# user_interface.net
KiCad netlist of a schematic drawn in Altium Designer
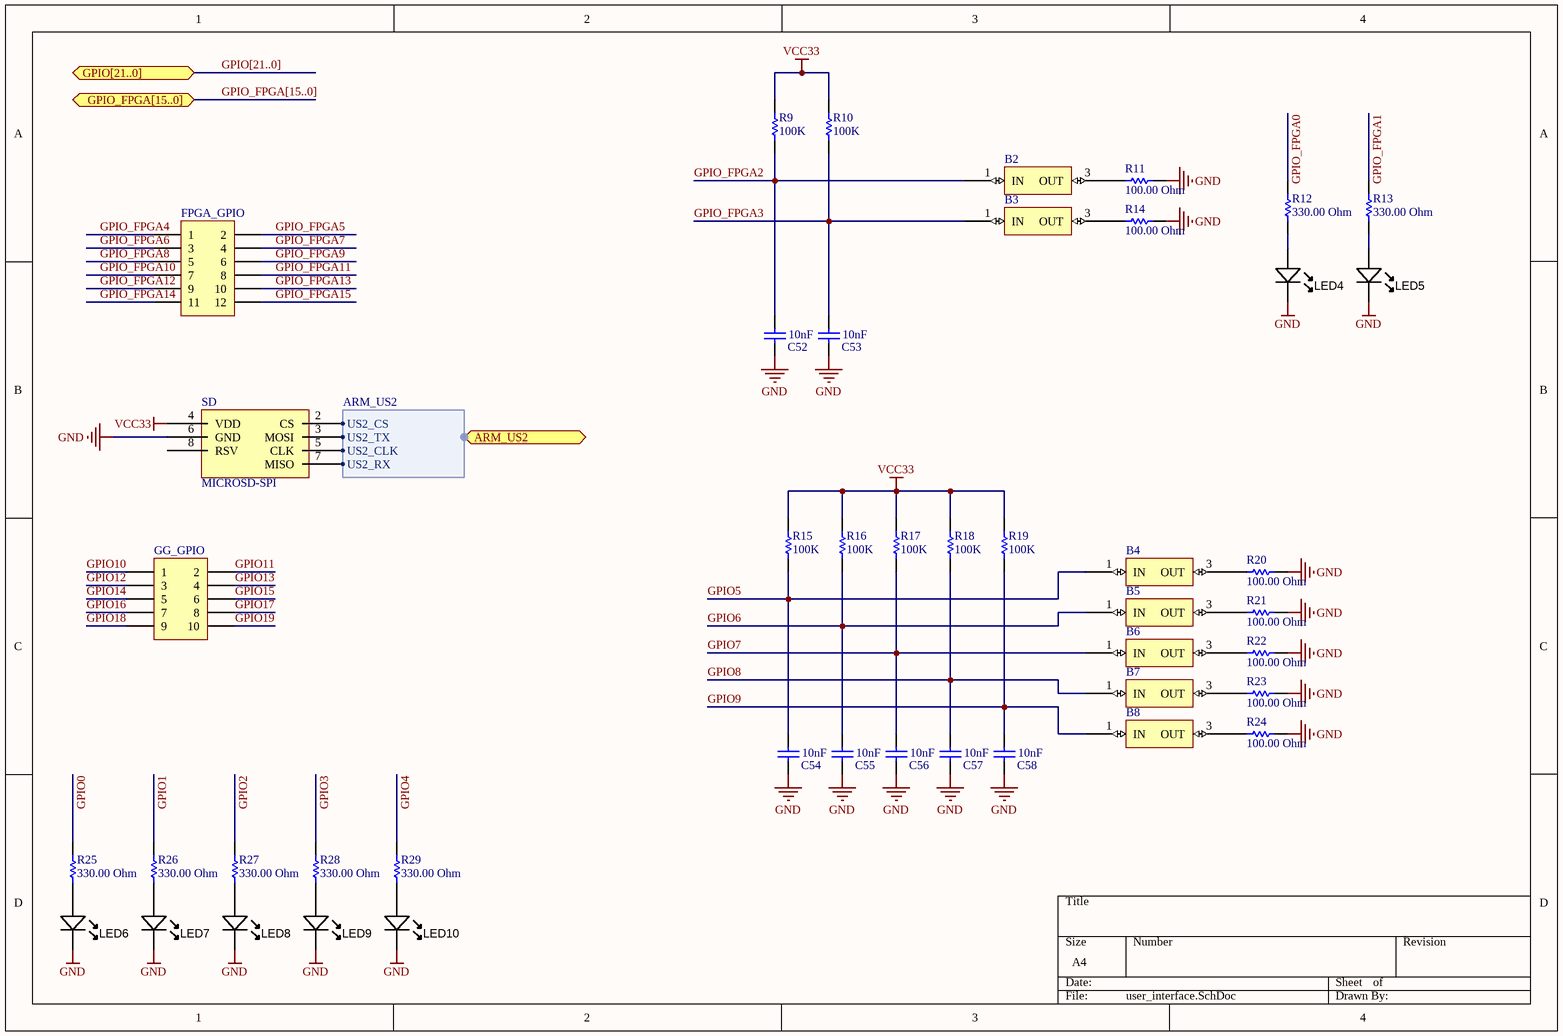
[diagram p0: user_interface.SchDoc]

(export (version "E")
  (design (tool "Eeschema 10.0.6"))
  (components
    (comp (ref "B2") (value "BUTTON") (footprint "BUTTON") (libsource (lib "PowerConnector") (part "BUTTON")))
    (comp (ref "B3") (value "BUTTON") (footprint "BUTTON") (libsource (lib "PowerConnector") (part "BUTTON")))
    (comp (ref "B4") (value "BUTTON") (footprint "BUTTON") (libsource (lib "PowerConnector") (part "BUTTON")))
    (comp (ref "B5") (value "BUTTON") (footprint "BUTTON") (libsource (lib "PowerConnector") (part "BUTTON")))
    (comp (ref "B6") (value "BUTTON") (footprint "BUTTON") (libsource (lib "PowerConnector") (part "BUTTON")))
    (comp (ref "B7") (value "BUTTON") (footprint "BUTTON") (libsource (lib "PowerConnector") (part "BUTTON")))
    (comp (ref "B8") (value "BUTTON") (footprint "BUTTON") (libsource (lib "PowerConnector") (part "BUTTON")))
    (comp (ref "C52")
      (value "10nF")
      (footprint "CAPC0805(2012)75_N")
      (description "CAP 10nF 50V ±10% 0805 (2012 Metric) Thickness 0.75mm SMD")
      (fields (field (name "TOLERANCE") "±10%"))
      (libsource (lib "Altium Content Vault") (part "CMP-1036-03842-1"))
    )
    (comp (ref "C53")
      (value "10nF")
      (footprint "CAPC0805(2012)75_N")
      (description "CAP 10nF 50V ±10% 0805 (2012 Metric) Thickness 0.75mm SMD")
      (fields (field (name "TOLERANCE") "±10%"))
      (libsource (lib "Altium Content Vault") (part "CMP-1036-03842-1"))
    )
    (comp (ref "C54")
      (value "10nF")
      (footprint "CAPC0805(2012)75_N")
      (description "CAP 10nF 50V ±10% 0805 (2012 Metric) Thickness 0.75mm SMD")
      (fields (field (name "TOLERANCE") "±10%"))
      (libsource (lib "Altium Content Vault") (part "CMP-1036-03842-1"))
    )
    (comp (ref "C55")
      (value "10nF")
      (footprint "CAPC0805(2012)75_N")
      (description "CAP 10nF 50V ±10% 0805 (2012 Metric) Thickness 0.75mm SMD")
      (fields (field (name "TOLERANCE") "±10%"))
      (libsource (lib "Altium Content Vault") (part "CMP-1036-03842-1"))
    )
    (comp (ref "C56")
      (value "10nF")
      (footprint "CAPC0805(2012)75_N")
      (description "CAP 10nF 50V ±10% 0805 (2012 Metric) Thickness 0.75mm SMD")
      (fields (field (name "TOLERANCE") "±10%"))
      (libsource (lib "Altium Content Vault") (part "CMP-1036-03842-1"))
    )
    (comp (ref "C57")
      (value "10nF")
      (footprint "CAPC0805(2012)75_N")
      (description "CAP 10nF 50V ±10% 0805 (2012 Metric) Thickness 0.75mm SMD")
      (fields (field (name "TOLERANCE") "±10%"))
      (libsource (lib "Altium Content Vault") (part "CMP-1036-03842-1"))
    )
    (comp (ref "C58")
      (value "10nF")
      (footprint "CAPC0805(2012)75_N")
      (description "CAP 10nF 50V ±10% 0805 (2012 Metric) Thickness 0.75mm SMD")
      (fields (field (name "TOLERANCE") "±10%"))
      (libsource (lib "Altium Content Vault") (part "CMP-1036-03842-1"))
    )
    (comp (ref "FPGA_GPIO")
      (value "Header 6X2")
      (footprint "HDR2X6")
      (description "Header, 6-Pin, Dual row")
      (fields (field (name "PUBLISHER") "Altium Limited"))
      (libsource (lib "Miscellaneous Connectors") (part "Header 6X2"))
    )
    (comp (ref "GG_GPIO")
      (value "Header 5X2")
      (footprint "HDR2X5")
      (description "Header, 5-Pin, Dual row")
      (fields (field (name "PUBLISHER") "Altium Limited"))
      (libsource (lib "Miscellaneous Connectors") (part "Header 5X2"))
    )
    (comp (ref "LED4")
      (value "Green")
      (footprint "LED-0805-K")
      (description "LED, 0805 SMD, Green")
      (libsource (lib "PBL - Light Sources") (part "LED_SMD_Green_0805"))
    )
    (comp (ref "LED5")
      (value "Green")
      (footprint "LED-0805-K")
      (description "LED, 0805 SMD, Green")
      (libsource (lib "PBL - Light Sources") (part "LED_SMD_Green_0805"))
    )
    (comp (ref "LED6")
      (value "Green")
      (footprint "LED-0805-K")
      (description "LED, 0805 SMD, Green")
      (libsource (lib "PBL - Light Sources") (part "LED_SMD_Green_0805"))
    )
    (comp (ref "LED7")
      (value "Green")
      (footprint "LED-0805-K")
      (description "LED, 0805 SMD, Green")
      (libsource (lib "PBL - Light Sources") (part "LED_SMD_Green_0805"))
    )
    (comp (ref "LED8")
      (value "Green")
      (footprint "LED-0805-K")
      (description "LED, 0805 SMD, Green")
      (libsource (lib "PBL - Light Sources") (part "LED_SMD_Green_0805"))
    )
    (comp (ref "LED9")
      (value "Green")
      (footprint "LED-0805-K")
      (description "LED, 0805 SMD, Green")
      (libsource (lib "PBL - Light Sources") (part "LED_SMD_Green_0805"))
    )
    (comp (ref "LED10")
      (value "Green")
      (footprint "LED-0805-K")
      (description "LED, 0805 SMD, Green")
      (libsource (lib "PBL - Light Sources") (part "LED_SMD_Green_0805"))
    )
    (comp (ref "R9")
      (value "100K")
      (footprint "RESC0805(2012)_L")
      (description "100K 0.125W 5% 0805 (2012 Metric)  SMD")
      (fields (field (name "TOLERANCE") "5 %") (field (name "POWER") "0.125 W"))
      (libsource (lib "Altium Content Vault") (part "CMP-1013-00122-1"))
    )
    (comp (ref "R10")
      (value "100K")
      (footprint "RESC0805(2012)_L")
      (description "100K 0.125W 5% 0805 (2012 Metric)  SMD")
      (fields (field (name "TOLERANCE") "5 %") (field (name "POWER") "0.125 W"))
      (libsource (lib "Altium Content Vault") (part "CMP-1013-00122-1"))
    )
    (comp (ref "R11")
      (value "100.00 Ohm")
      (footprint "RESC0805(2012)_M")
      (description "100R 0.125W 5% 0805 (2012 Metric)  SMD")
      (fields (field (name "TOLERANCE") "5 %") (field (name "POWER") "0.125 W"))
      (libsource (lib "Altium Content Vault") (part "CMP-1013-00050-1"))
    )
    (comp (ref "R12")
      (value "330.00 Ohm")
      (footprint "RESC0805(2012)_M")
      (description "330R 0.125W 1% 0805 (2012 Metric)  SMD")
      (fields (field (name "POWER") "0.125 W") (field (name "TOLERANCE") "1 %"))
      (libsource (lib "Altium Content Vault") (part "CMP-1013-00454-1"))
    )
    (comp (ref "R13")
      (value "330.00 Ohm")
      (footprint "RESC0805(2012)_M")
      (description "330R 0.125W 1% 0805 (2012 Metric)  SMD")
      (fields (field (name "POWER") "0.125 W") (field (name "TOLERANCE") "1 %"))
      (libsource (lib "Altium Content Vault") (part "CMP-1013-00454-1"))
    )
    (comp (ref "R14")
      (value "100.00 Ohm")
      (footprint "RESC0805(2012)_M")
      (description "100R 0.125W 5% 0805 (2012 Metric)  SMD")
      (fields (field (name "TOLERANCE") "5 %") (field (name "POWER") "0.125 W"))
      (libsource (lib "Altium Content Vault") (part "CMP-1013-00050-1"))
    )
    (comp (ref "R15")
      (value "100K")
      (footprint "RESC0805(2012)_L")
      (description "100K 0.125W 5% 0805 (2012 Metric)  SMD")
      (fields (field (name "TOLERANCE") "5 %") (field (name "POWER") "0.125 W"))
      (libsource (lib "Altium Content Vault") (part "CMP-1013-00122-1"))
    )
    (comp (ref "R16")
      (value "100K")
      (footprint "RESC0805(2012)_L")
      (description "100K 0.125W 5% 0805 (2012 Metric)  SMD")
      (fields (field (name "TOLERANCE") "5 %") (field (name "POWER") "0.125 W"))
      (libsource (lib "Altium Content Vault") (part "CMP-1013-00122-1"))
    )
    (comp (ref "R17")
      (value "100K")
      (footprint "RESC0805(2012)_L")
      (description "100K 0.125W 5% 0805 (2012 Metric)  SMD")
      (fields (field (name "TOLERANCE") "5 %") (field (name "POWER") "0.125 W"))
      (libsource (lib "Altium Content Vault") (part "CMP-1013-00122-1"))
    )
    (comp (ref "R18")
      (value "100K")
      (footprint "RESC0805(2012)_L")
      (description "100K 0.125W 5% 0805 (2012 Metric)  SMD")
      (fields (field (name "TOLERANCE") "5 %") (field (name "POWER") "0.125 W"))
      (libsource (lib "Altium Content Vault") (part "CMP-1013-00122-1"))
    )
    (comp (ref "R19")
      (value "100K")
      (footprint "RESC0805(2012)_L")
      (description "100K 0.125W 5% 0805 (2012 Metric)  SMD")
      (fields (field (name "TOLERANCE") "5 %") (field (name "POWER") "0.125 W"))
      (libsource (lib "Altium Content Vault") (part "CMP-1013-00122-1"))
    )
    (comp (ref "R20")
      (value "100.00 Ohm")
      (footprint "RESC0805(2012)_M")
      (description "100R 0.125W 5% 0805 (2012 Metric)  SMD")
      (fields (field (name "TOLERANCE") "5 %") (field (name "POWER") "0.125 W"))
      (libsource (lib "Altium Content Vault") (part "CMP-1013-00050-1"))
    )
    (comp (ref "R21")
      (value "100.00 Ohm")
      (footprint "RESC0805(2012)_M")
      (description "100R 0.125W 5% 0805 (2012 Metric)  SMD")
      (fields (field (name "TOLERANCE") "5 %") (field (name "POWER") "0.125 W"))
      (libsource (lib "Altium Content Vault") (part "CMP-1013-00050-1"))
    )
    (comp (ref "R22")
      (value "100.00 Ohm")
      (footprint "RESC0805(2012)_M")
      (description "100R 0.125W 5% 0805 (2012 Metric)  SMD")
      (fields (field (name "TOLERANCE") "5 %") (field (name "POWER") "0.125 W"))
      (libsource (lib "Altium Content Vault") (part "CMP-1013-00050-1"))
    )
    (comp (ref "R23")
      (value "100.00 Ohm")
      (footprint "RESC0805(2012)_M")
      (description "100R 0.125W 5% 0805 (2012 Metric)  SMD")
      (fields (field (name "TOLERANCE") "5 %") (field (name "POWER") "0.125 W"))
      (libsource (lib "Altium Content Vault") (part "CMP-1013-00050-1"))
    )
    (comp (ref "R24")
      (value "100.00 Ohm")
      (footprint "RESC0805(2012)_M")
      (description "100R 0.125W 5% 0805 (2012 Metric)  SMD")
      (fields (field (name "TOLERANCE") "5 %") (field (name "POWER") "0.125 W"))
      (libsource (lib "Altium Content Vault") (part "CMP-1013-00050-1"))
    )
    (comp (ref "R25")
      (value "330.00 Ohm")
      (footprint "RESC0805(2012)_M")
      (description "330R 0.125W 1% 0805 (2012 Metric)  SMD")
      (fields (field (name "POWER") "0.125 W") (field (name "TOLERANCE") "1 %"))
      (libsource (lib "Altium Content Vault") (part "CMP-1013-00454-1"))
    )
    (comp (ref "R26")
      (value "330.00 Ohm")
      (footprint "RESC0805(2012)_M")
      (description "330R 0.125W 1% 0805 (2012 Metric)  SMD")
      (fields (field (name "POWER") "0.125 W") (field (name "TOLERANCE") "1 %"))
      (libsource (lib "Altium Content Vault") (part "CMP-1013-00454-1"))
    )
    (comp (ref "R27")
      (value "330.00 Ohm")
      (footprint "RESC0805(2012)_M")
      (description "330R 0.125W 1% 0805 (2012 Metric)  SMD")
      (fields (field (name "POWER") "0.125 W") (field (name "TOLERANCE") "1 %"))
      (libsource (lib "Altium Content Vault") (part "CMP-1013-00454-1"))
    )
    (comp (ref "R28")
      (value "330.00 Ohm")
      (footprint "RESC0805(2012)_M")
      (description "330R 0.125W 1% 0805 (2012 Metric)  SMD")
      (fields (field (name "POWER") "0.125 W") (field (name "TOLERANCE") "1 %"))
      (libsource (lib "Altium Content Vault") (part "CMP-1013-00454-1"))
    )
    (comp (ref "R29")
      (value "330.00 Ohm")
      (footprint "RESC0805(2012)_M")
      (description "330R 0.125W 1% 0805 (2012 Metric)  SMD")
      (fields (field (name "POWER") "0.125 W") (field (name "TOLERANCE") "1 %"))
      (libsource (lib "Altium Content Vault") (part "CMP-1013-00454-1"))
    )
    (comp (ref "SD")
      (value "MICROSD-SPI")
      (footprint "MICROSD_WR-CRD")
      (libsource (lib "MICROSD") (part "MICROSD-SPI"))
    )
  )
  (nets
    (net (code "4") (name "/GPIO0") (class "Default")
      (node (ref "R25") (pin "2") (pinfunction "2_2") (pintype "passive"))
    )
    (net (code "5") (name "/GPIO1") (class "Default")
      (node (ref "R26") (pin "2") (pinfunction "2_2") (pintype "passive"))
    )
    (net (code "6") (name "/GPIO2") (class "Default")
      (node (ref "R27") (pin "2") (pinfunction "2_2") (pintype "passive"))
    )
    (net (code "7") (name "/GPIO3") (class "Default")
      (node (ref "R28") (pin "2") (pinfunction "2_2") (pintype "passive"))
    )
    (net (code "8") (name "/GPIO4") (class "Default")
      (node (ref "R29") (pin "2") (pinfunction "2_2") (pintype "passive"))
    )
    (net (code "9") (name "/GPIO5") (class "Default")
      (node (ref "B4") (pin "1") (pinfunction "IN_1") (pintype "bidirectional"))
      (node (ref "C54") (pin "2") (pinfunction "2_2") (pintype "passive"))
      (node (ref "R15") (pin "1") (pinfunction "1_1") (pintype "passive"))
    )
    (net (code "10") (name "/GPIO6") (class "Default")
      (node (ref "B5") (pin "1") (pinfunction "IN_1") (pintype "bidirectional"))
      (node (ref "C55") (pin "2") (pinfunction "2_2") (pintype "passive"))
      (node (ref "R16") (pin "1") (pinfunction "1_1") (pintype "passive"))
    )
    (net (code "11") (name "/GPIO7") (class "Default")
      (node (ref "B6") (pin "1") (pinfunction "IN_1") (pintype "bidirectional"))
      (node (ref "C56") (pin "2") (pinfunction "2_2") (pintype "passive"))
      (node (ref "R17") (pin "1") (pinfunction "1_1") (pintype "passive"))
    )
    (net (code "12") (name "/GPIO8") (class "Default")
      (node (ref "B7") (pin "1") (pinfunction "IN_1") (pintype "bidirectional"))
      (node (ref "C57") (pin "2") (pinfunction "2_2") (pintype "passive"))
      (node (ref "R18") (pin "1") (pinfunction "1_1") (pintype "passive"))
    )
    (net (code "13") (name "/GPIO9") (class "Default")
      (node (ref "B8") (pin "1") (pinfunction "IN_1") (pintype "bidirectional"))
      (node (ref "C58") (pin "2") (pinfunction "2_2") (pintype "passive"))
      (node (ref "R19") (pin "1") (pinfunction "1_1") (pintype "passive"))
    )
    (net (code "14") (name "/GPIO10") (class "Default")
      (node (ref "GG_GPIO") (pin "1") (pinfunction "1_1") (pintype "passive"))
    )
    (net (code "15") (name "/GPIO11") (class "Default")
      (node (ref "GG_GPIO") (pin "2") (pinfunction "2_2") (pintype "passive"))
    )
    (net (code "16") (name "/GPIO12") (class "Default")
      (node (ref "GG_GPIO") (pin "3") (pinfunction "3_3") (pintype "passive"))
    )
    (net (code "17") (name "/GPIO13") (class "Default")
      (node (ref "GG_GPIO") (pin "4") (pinfunction "4_4") (pintype "passive"))
    )
    (net (code "18") (name "/GPIO14") (class "Default")
      (node (ref "GG_GPIO") (pin "5") (pinfunction "5_5") (pintype "passive"))
    )
    (net (code "19") (name "/GPIO15") (class "Default")
      (node (ref "GG_GPIO") (pin "6") (pinfunction "6_6") (pintype "passive"))
    )
    (net (code "20") (name "/GPIO16") (class "Default")
      (node (ref "GG_GPIO") (pin "7") (pinfunction "7_7") (pintype "passive"))
    )
    (net (code "21") (name "/GPIO17") (class "Default")
      (node (ref "GG_GPIO") (pin "8") (pinfunction "8_8") (pintype "passive"))
    )
    (net (code "22") (name "/GPIO18") (class "Default")
      (node (ref "GG_GPIO") (pin "9") (pinfunction "9_9") (pintype "passive"))
    )
    (net (code "23") (name "/GPIO19") (class "Default")
      (node (ref "GG_GPIO") (pin "10") (pinfunction "10_10") (pintype "passive"))
    )
    (net (code "25") (name "/GPIO_FPGA0") (class "Default")
      (node (ref "R12") (pin "2") (pinfunction "2_2") (pintype "passive"))
    )
    (net (code "26") (name "/GPIO_FPGA1") (class "Default")
      (node (ref "R13") (pin "2") (pinfunction "2_2") (pintype "passive"))
    )
    (net (code "27") (name "/GPIO_FPGA2") (class "Default")
      (node (ref "B2") (pin "1") (pinfunction "IN_1") (pintype "bidirectional"))
      (node (ref "C52") (pin "2") (pinfunction "2_2") (pintype "passive"))
      (node (ref "R9") (pin "1") (pinfunction "1_1") (pintype "passive"))
    )
    (net (code "28") (name "/GPIO_FPGA3") (class "Default")
      (node (ref "B3") (pin "1") (pinfunction "IN_1") (pintype "bidirectional"))
      (node (ref "C53") (pin "2") (pinfunction "2_2") (pintype "passive"))
      (node (ref "R10") (pin "1") (pinfunction "1_1") (pintype "passive"))
    )
    (net (code "29") (name "/GPIO_FPGA4") (class "Default")
      (node (ref "FPGA_GPIO") (pin "1") (pinfunction "1_1") (pintype "passive"))
    )
    (net (code "30") (name "/GPIO_FPGA5") (class "Default")
      (node (ref "FPGA_GPIO") (pin "2") (pinfunction "2_2") (pintype "passive"))
    )
    (net (code "31") (name "/GPIO_FPGA6") (class "Default")
      (node (ref "FPGA_GPIO") (pin "3") (pinfunction "3_3") (pintype "passive"))
    )
    (net (code "32") (name "/GPIO_FPGA7") (class "Default")
      (node (ref "FPGA_GPIO") (pin "4") (pinfunction "4_4") (pintype "passive"))
    )
    (net (code "33") (name "/GPIO_FPGA8") (class "Default")
      (node (ref "FPGA_GPIO") (pin "5") (pinfunction "5_5") (pintype "passive"))
    )
    (net (code "34") (name "/GPIO_FPGA9") (class "Default")
      (node (ref "FPGA_GPIO") (pin "6") (pinfunction "6_6") (pintype "passive"))
    )
    (net (code "35") (name "/GPIO_FPGA10") (class "Default")
      (node (ref "FPGA_GPIO") (pin "7") (pinfunction "7_7") (pintype "passive"))
    )
    (net (code "36") (name "/GPIO_FPGA11") (class "Default")
      (node (ref "FPGA_GPIO") (pin "8") (pinfunction "8_8") (pintype "passive"))
    )
    (net (code "37") (name "/GPIO_FPGA12") (class "Default")
      (node (ref "FPGA_GPIO") (pin "9") (pinfunction "9_9") (pintype "passive"))
    )
    (net (code "38") (name "/GPIO_FPGA13") (class "Default")
      (node (ref "FPGA_GPIO") (pin "10") (pinfunction "10_10") (pintype "passive"))
    )
    (net (code "39") (name "/GPIO_FPGA14") (class "Default")
      (node (ref "FPGA_GPIO") (pin "11") (pinfunction "11_11") (pintype "passive"))
    )
    (net (code "40") (name "/GPIO_FPGA15") (class "Default")
      (node (ref "FPGA_GPIO") (pin "12") (pinfunction "12_12") (pintype "passive"))
    )
    (net (code "42") (name "/US2_CLK") (class "Default")
      (node (ref "SD") (pin "5") (pinfunction "CLK_5") (pintype "passive"))
    )
    (net (code "43") (name "/US2_CS") (class "Default")
      (node (ref "SD") (pin "2") (pinfunction "CS_2") (pintype "passive"))
    )
    (net (code "44") (name "/US2_RX") (class "Default")
      (node (ref "SD") (pin "7") (pinfunction "MISO_7") (pintype "passive"))
    )
    (net (code "45") (name "/US2_TX") (class "Default")
      (node (ref "SD") (pin "3") (pinfunction "MOSI_3") (pintype "passive"))
    )
    (net (code "47") (name "GND") (class "Default")
      (node (ref "C52") (pin "1") (pinfunction "1_1") (pintype "passive"))
      (node (ref "C53") (pin "1") (pinfunction "1_1") (pintype "passive"))
      (node (ref "C54") (pin "1") (pinfunction "1_1") (pintype "passive"))
      (node (ref "C55") (pin "1") (pinfunction "1_1") (pintype "passive"))
      (node (ref "C56") (pin "1") (pinfunction "1_1") (pintype "passive"))
      (node (ref "C57") (pin "1") (pinfunction "1_1") (pintype "passive"))
      (node (ref "C58") (pin "1") (pinfunction "1_1") (pintype "passive"))
      (node (ref "LED10") (pin "K") (pinfunction "K_K") (pintype "passive"))
      (node (ref "LED4") (pin "K") (pinfunction "K_K") (pintype "passive"))
      (node (ref "LED5") (pin "K") (pinfunction "K_K") (pintype "passive"))
      (node (ref "LED6") (pin "K") (pinfunction "K_K") (pintype "passive"))
      (node (ref "LED7") (pin "K") (pinfunction "K_K") (pintype "passive"))
      (node (ref "LED8") (pin "K") (pinfunction "K_K") (pintype "passive"))
      (node (ref "LED9") (pin "K") (pinfunction "K_K") (pintype "passive"))
      (node (ref "R11") (pin "2") (pinfunction "2_2") (pintype "passive"))
      (node (ref "R14") (pin "2") (pinfunction "2_2") (pintype "passive"))
      (node (ref "R20") (pin "2") (pinfunction "2_2") (pintype "passive"))
      (node (ref "R21") (pin "2") (pinfunction "2_2") (pintype "passive"))
      (node (ref "R22") (pin "2") (pinfunction "2_2") (pintype "passive"))
      (node (ref "R23") (pin "2") (pinfunction "2_2") (pintype "passive"))
      (node (ref "R24") (pin "2") (pinfunction "2_2") (pintype "passive"))
      (node (ref "SD") (pin "6") (pinfunction "GND_6") (pintype "passive"))
    )
    (net (code "48") (name "Net-(B2-OUT)") (class "Default")
      (node (ref "B2") (pin "3") (pinfunction "OUT_3") (pintype "bidirectional"))
      (node (ref "R11") (pin "1") (pinfunction "1_1") (pintype "passive"))
    )
    (net (code "49") (name "Net-(B3-OUT)") (class "Default")
      (node (ref "B3") (pin "3") (pinfunction "OUT_3") (pintype "bidirectional"))
      (node (ref "R14") (pin "1") (pinfunction "1_1") (pintype "passive"))
    )
    (net (code "50") (name "Net-(B4-OUT)") (class "Default")
      (node (ref "B4") (pin "3") (pinfunction "OUT_3") (pintype "bidirectional"))
      (node (ref "R20") (pin "1") (pinfunction "1_1") (pintype "passive"))
    )
    (net (code "51") (name "Net-(B5-OUT)") (class "Default")
      (node (ref "B5") (pin "3") (pinfunction "OUT_3") (pintype "bidirectional"))
      (node (ref "R21") (pin "1") (pinfunction "1_1") (pintype "passive"))
    )
    (net (code "52") (name "Net-(B6-OUT)") (class "Default")
      (node (ref "B6") (pin "3") (pinfunction "OUT_3") (pintype "bidirectional"))
      (node (ref "R22") (pin "1") (pinfunction "1_1") (pintype "passive"))
    )
    (net (code "53") (name "Net-(B7-OUT)") (class "Default")
      (node (ref "B7") (pin "3") (pinfunction "OUT_3") (pintype "bidirectional"))
      (node (ref "R23") (pin "1") (pinfunction "1_1") (pintype "passive"))
    )
    (net (code "54") (name "Net-(B8-OUT)") (class "Default")
      (node (ref "B8") (pin "3") (pinfunction "OUT_3") (pintype "bidirectional"))
      (node (ref "R24") (pin "1") (pinfunction "1_1") (pintype "passive"))
    )
    (net (code "55") (name "Net-(LED4-PadA)") (class "Default")
      (node (ref "LED4") (pin "A") (pinfunction "A_A") (pintype "passive"))
      (node (ref "R12") (pin "1") (pinfunction "1_1") (pintype "passive"))
    )
    (net (code "56") (name "Net-(LED5-PadA)") (class "Default")
      (node (ref "LED5") (pin "A") (pinfunction "A_A") (pintype "passive"))
      (node (ref "R13") (pin "1") (pinfunction "1_1") (pintype "passive"))
    )
    (net (code "57") (name "Net-(LED6-PadA)") (class "Default")
      (node (ref "LED6") (pin "A") (pinfunction "A_A") (pintype "passive"))
      (node (ref "R25") (pin "1") (pinfunction "1_1") (pintype "passive"))
    )
    (net (code "58") (name "Net-(LED7-PadA)") (class "Default")
      (node (ref "LED7") (pin "A") (pinfunction "A_A") (pintype "passive"))
      (node (ref "R26") (pin "1") (pinfunction "1_1") (pintype "passive"))
    )
    (net (code "59") (name "Net-(LED8-PadA)") (class "Default")
      (node (ref "LED8") (pin "A") (pinfunction "A_A") (pintype "passive"))
      (node (ref "R27") (pin "1") (pinfunction "1_1") (pintype "passive"))
    )
    (net (code "60") (name "Net-(LED9-PadA)") (class "Default")
      (node (ref "LED9") (pin "A") (pinfunction "A_A") (pintype "passive"))
      (node (ref "R28") (pin "1") (pinfunction "1_1") (pintype "passive"))
    )
    (net (code "61") (name "Net-(LED10-PadA)") (class "Default")
      (node (ref "LED10") (pin "A") (pinfunction "A_A") (pintype "passive"))
      (node (ref "R29") (pin "1") (pinfunction "1_1") (pintype "passive"))
    )
    (net (code "62") (name "VCC33") (class "Default")
      (node (ref "R10") (pin "2") (pinfunction "2_2") (pintype "passive"))
      (node (ref "R15") (pin "2") (pinfunction "2_2") (pintype "passive"))
      (node (ref "R16") (pin "2") (pinfunction "2_2") (pintype "passive"))
      (node (ref "R17") (pin "2") (pinfunction "2_2") (pintype "passive"))
      (node (ref "R18") (pin "2") (pinfunction "2_2") (pintype "passive"))
      (node (ref "R19") (pin "2") (pinfunction "2_2") (pintype "passive"))
      (node (ref "R9") (pin "2") (pinfunction "2_2") (pintype "passive"))
      (node (ref "SD") (pin "4") (pinfunction "VDD_4") (pintype "passive"))
    )
    (net (code "63") (name "unconnected-(SD-RSV-Pad8)") (class "Default")
      (node (ref "SD") (pin "8") (pinfunction "RSV_8") (pintype "passive"))
    )
  )
)
